# Supplies_ADP2164.net
KiCad netlist of a schematic drawn in Altium Designer
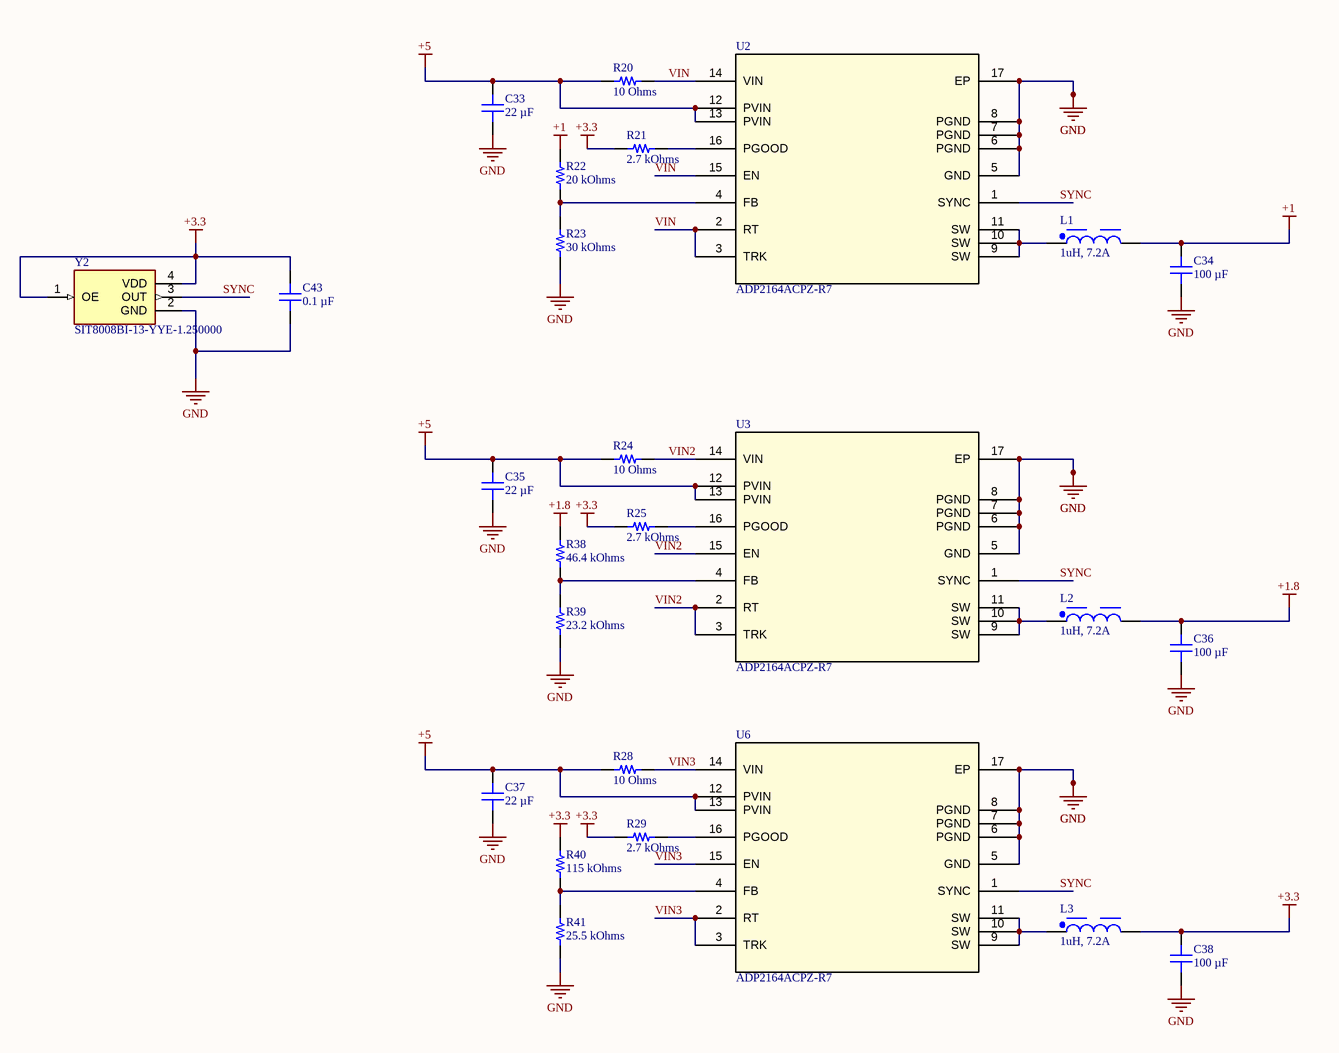
[diagram p0: Supplies_ADP2164.SchDoc]

(export (version "E")
  (design (tool "Eeschema 10.0.6"))
  (components
    (comp (ref "C33")
      (value "22 µF")
      (footprint "CAP 0603_1608")
      (description "CAP CER 22UF 10V X5R 0603")
      (fields
        (field (name "PART NUMBER") "GRM187R61A226ME15D")
        (field (name "MANUFACTURER") "Murata Electronics")
      )
      (libsource (lib "Celestial Altium Library - altium_library") (part "Capacitor"))
    )
    (comp (ref "C34")
      (value "100 µF")
      (footprint "CAP 1210_3225 - 1MM")
      (description "CAP CER 100UF 10V X5R 1210")
      (fields
        (field (name "PART NUMBER") "GRM32ER61A107ME20K")
        (field (name "MANUFACTURER") "Murata Electronics")
      )
      (libsource (lib "Celestial Altium Library - altium_library") (part "Capacitor"))
    )
    (comp (ref "C35")
      (value "22 µF")
      (footprint "CAP 0603_1608")
      (description "CAP CER 22UF 10V X5R 0603")
      (fields
        (field (name "PART NUMBER") "GRM187R61A226ME15D")
        (field (name "MANUFACTURER") "Murata Electronics")
      )
      (libsource (lib "Celestial Altium Library - altium_library") (part "Capacitor"))
    )
    (comp (ref "C36")
      (value "100 µF")
      (footprint "CAP 1210_3225 - 1MM")
      (description "CAP CER 100UF 10V X5R 1210")
      (fields
        (field (name "PART NUMBER") "GRM32ER61A107ME20K")
        (field (name "MANUFACTURER") "Murata Electronics")
      )
      (libsource (lib "Celestial Altium Library - altium_library") (part "Capacitor"))
    )
    (comp (ref "C37")
      (value "22 µF")
      (footprint "CAP 0603_1608")
      (description "CAP CER 22UF 10V X5R 0603")
      (fields
        (field (name "PART NUMBER") "GRM187R61A226ME15D")
        (field (name "MANUFACTURER") "Murata Electronics")
      )
      (libsource (lib "Celestial Altium Library - altium_library") (part "Capacitor"))
    )
    (comp (ref "C38")
      (value "100 µF")
      (footprint "CAP 1210_3225 - 1MM")
      (description "CAP CER 100UF 10V X5R 1210")
      (fields
        (field (name "PART NUMBER") "GRM32ER61A107ME20K")
        (field (name "MANUFACTURER") "Murata Electronics")
      )
      (libsource (lib "Celestial Altium Library - altium_library") (part "Capacitor"))
    )
    (comp (ref "C43")
      (value "0.1 µF")
      (footprint "CAP 0201_0603")
      (description "CAP CER 0.1UF 10V X5R 0201")
      (fields
        (field (name "PART NUMBER") "GRM033R61A104KE15D")
        (field (name "MANUFACTURER") "Murata Electronics")
      )
      (libsource (lib "Celestial Altium Library - altium_library") (part "Capacitor"))
    )
    (comp (ref "L1")
      (value "1uH, 7.2A")
      (footprint "WE-MAPI_4020")
      (description "WE-MAPI SMT Power Inductor, size 4020, 1uH, 7.2A")
      (fields
        (field (name "MANUFACTURER") "Wurth Elektronik")
        (field (name "MANUFACTURER PART NUMBER") "74438356010")
      )
      (libsource (lib "WE-MAPI (rev22a)") (part "74438356010"))
    )
    (comp (ref "L2")
      (value "1uH, 7.2A")
      (footprint "WE-MAPI_4020")
      (description "WE-MAPI SMT Power Inductor, size 4020, 1uH, 7.2A")
      (fields
        (field (name "MANUFACTURER") "Wurth Elektronik")
        (field (name "MANUFACTURER PART NUMBER") "74438356010")
      )
      (libsource (lib "WE-MAPI (rev22a)") (part "74438356010"))
    )
    (comp (ref "L3")
      (value "1uH, 7.2A")
      (footprint "WE-MAPI_4020")
      (description "WE-MAPI SMT Power Inductor, size 4020, 1uH, 7.2A")
      (fields
        (field (name "MANUFACTURER") "Wurth Elektronik")
        (field (name "MANUFACTURER PART NUMBER") "74438356010")
      )
      (libsource (lib "WE-MAPI (rev22a)") (part "74438356010"))
    )
    (comp (ref "R20")
      (value "10 Ohms")
      (footprint "RES 0201_0603")
      (description "RES 10 OHM 5% 1/20W 0201")
      (fields (field (name "PART NUMBER") "RC0201JR-0710RL") (field (name "MANUFACTURER") "Yageo"))
      (libsource (lib "Celestial Altium Library - altium_library") (part "Resistor"))
    )
    (comp (ref "R21")
      (value "2.7 kOhms")
      (footprint "RES 0201_0603")
      (description "RES 2.7K OHM 5% 1/20W 0201 SMD")
      (fields
        (field (name "PART NUMBER") "ERJ-U01J272C")
        (field (name "MANUFACTURER") "Panasonic Electronic Components")
      )
      (libsource (lib "Celestial Altium Library - altium_library") (part "Resistor"))
    )
    (comp (ref "R22")
      (value "20 kOhms")
      (footprint "RES 0201_0603")
      (description "RES SMD 20K OHM 1% 1/20W 0201")
      (fields
        (field (name "PART NUMBER") "ERJ-1GNF2002C")
        (field (name "MANUFACTURER") "Panasonic Electronic Components")
      )
      (libsource (lib "Celestial Altium Library - altium_library") (part "Resistor"))
    )
    (comp (ref "R23")
      (value "30 kOhms")
      (footprint "RES 0201_0603")
      (description "RES SMD 30K OHM 1% 1/20W 0201")
      (fields
        (field (name "PART NUMBER") "ERJ-1GNF3002C")
        (field (name "MANUFACTURER") "Panasonic Electronic Components")
      )
      (libsource (lib "Celestial Altium Library - altium_library") (part "Resistor"))
    )
    (comp (ref "R24")
      (value "10 Ohms")
      (footprint "RES 0201_0603")
      (description "RES 10 OHM 5% 1/20W 0201")
      (fields (field (name "PART NUMBER") "RC0201JR-0710RL") (field (name "MANUFACTURER") "Yageo"))
      (libsource (lib "Celestial Altium Library - altium_library") (part "Resistor"))
    )
    (comp (ref "R25")
      (value "2.7 kOhms")
      (footprint "RES 0201_0603")
      (description "RES 2.7K OHM 5% 1/20W 0201 SMD")
      (fields
        (field (name "PART NUMBER") "ERJ-U01J272C")
        (field (name "MANUFACTURER") "Panasonic Electronic Components")
      )
      (libsource (lib "Celestial Altium Library - altium_library") (part "Resistor"))
    )
    (comp (ref "R28")
      (value "10 Ohms")
      (footprint "RES 0201_0603")
      (description "RES 10 OHM 5% 1/20W 0201")
      (fields (field (name "PART NUMBER") "RC0201JR-0710RL") (field (name "MANUFACTURER") "Yageo"))
      (libsource (lib "Celestial Altium Library - altium_library") (part "Resistor"))
    )
    (comp (ref "R29")
      (value "2.7 kOhms")
      (footprint "RES 0201_0603")
      (description "RES 2.7K OHM 5% 1/20W 0201 SMD")
      (fields
        (field (name "PART NUMBER") "ERJ-U01J272C")
        (field (name "MANUFACTURER") "Panasonic Electronic Components")
      )
      (libsource (lib "Celestial Altium Library - altium_library") (part "Resistor"))
    )
    (comp (ref "R38")
      (value "46.4 kOhms")
      (footprint "RES 0201_0603")
      (description "RES SMD 46.4K OHM 1% 1/20W 0201")
      (fields
        (field (name "PART NUMBER") "ERJ-1GNF4642C")
        (field (name "MANUFACTURER") "Panasonic Electronic Components")
      )
      (libsource (lib "Celestial Altium Library - altium_library") (part "Resistor"))
    )
    (comp (ref "R39")
      (value "23.2 kOhms")
      (footprint "RES 0201_0603")
      (description "RES SMD 23.2K OHM 1% 1/20W 0201")
      (fields
        (field (name "PART NUMBER") "ERJ-1GNF2322C")
        (field (name "MANUFACTURER") "Panasonic Electronic Components")
      )
      (libsource (lib "Celestial Altium Library - altium_library") (part "Resistor"))
    )
    (comp (ref "R40")
      (value "115 kOhms")
      (footprint "RES 0201_0603")
      (description "RES SMD 115K OHM 1% 1/20W 0201")
      (fields
        (field (name "PART NUMBER") "ERJ-1GNF1153C")
        (field (name "MANUFACTURER") "Panasonic Electronic Components")
      )
      (libsource (lib "Celestial Altium Library - altium_library") (part "Resistor"))
    )
    (comp (ref "R41")
      (value "25.5 kOhms")
      (footprint "RES 0201_0603")
      (description "RES SMD 25.5K OHM 1% 1/20W 0201")
      (fields
        (field (name "PART NUMBER") "ERJ-1GNF2552C")
        (field (name "MANUFACTURER") "Panasonic Electronic Components")
      )
      (libsource (lib "Celestial Altium Library - altium_library") (part "Resistor"))
    )
    (comp (ref "U2")
      (value "ADP2164ACPZ-R7")
      (footprint "CP_16_17_ADI")
      (description "No Description Available")
      (fields (field (name "COPYRIGHT") "Copyright (C) 2022 Ultra Librarian. All rights reserved."))
      (libsource (lib "ADP2164ACPZ-R7") (part "ADP2164ACPZ-R7"))
    )
    (comp (ref "U3")
      (value "ADP2164ACPZ-R7")
      (footprint "CP_16_17_ADI")
      (description "No Description Available")
      (fields (field (name "COPYRIGHT") "Copyright (C) 2022 Ultra Librarian. All rights reserved."))
      (libsource (lib "ADP2164ACPZ-R7") (part "ADP2164ACPZ-R7"))
    )
    (comp (ref "U6")
      (value "ADP2164ACPZ-R7")
      (footprint "CP_16_17_ADI")
      (description "No Description Available")
      (fields (field (name "COPYRIGHT") "Copyright (C) 2022 Ultra Librarian. All rights reserved."))
      (libsource (lib "ADP2164ACPZ-R7") (part "ADP2164ACPZ-R7"))
    )
    (comp (ref "Y2")
      (value "SIT8008BI-13-YYE-1.250000")
      (footprint "SIT8008BI-13-33E-33.333330E:OSC_SIT8008BI-13-33E-33.333330E")
      (description "Programmable, Low Power Oscillator, -40 To 85c, 2520, 50ppm, 3.3v, 33.33333mhz, Oe, Smd")
      (fields
        (field (name "MF") "{'manufacturer': u'SiTIME'}")
        (field (name "MP") "SIT8008BI-13-33E-33.333330E")
      )
      (libsource (lib "SIT8008BI-13-33E-33.333330E") (part "SIT8008BI-13-33E-33.333330E"))
    )
  )
  (nets
    (net (code "1") (name "+1") (class "Default")
      (node (ref "C34") (pin "2") (pinfunction "2_2") (pintype "passive"))
      (node (ref "L1") (pin "2") (pinfunction "2_2") (pintype "passive"))
      (node (ref "R22") (pin "2") (pinfunction "2_2") (pintype "passive"))
    )
    (net (code "2") (name "+1.8") (class "Default")
      (node (ref "C36") (pin "2") (pinfunction "2_2") (pintype "passive"))
      (node (ref "L2") (pin "2") (pinfunction "2_2") (pintype "passive"))
      (node (ref "R38") (pin "2") (pinfunction "2_2") (pintype "passive"))
    )
    (net (code "3") (name "+3.3") (class "Default")
      (node (ref "C38") (pin "2") (pinfunction "2_2") (pintype "passive"))
      (node (ref "C43") (pin "2") (pinfunction "2_2") (pintype "passive"))
      (node (ref "L3") (pin "2") (pinfunction "2_2") (pintype "passive"))
      (node (ref "R21") (pin "2") (pinfunction "2_2") (pintype "passive"))
      (node (ref "R25") (pin "2") (pinfunction "2_2") (pintype "passive"))
      (node (ref "R29") (pin "2") (pinfunction "2_2") (pintype "passive"))
      (node (ref "R40") (pin "2") (pinfunction "2_2") (pintype "passive"))
      (node (ref "Y2") (pin "1") (pinfunction "OE_1") (pintype "input"))
      (node (ref "Y2") (pin "4") (pinfunction "VDD_4") (pintype "power_in"))
    )
    (net (code "4") (name "+5") (class "Default")
      (node (ref "C33") (pin "2") (pinfunction "2_2") (pintype "passive"))
      (node (ref "C35") (pin "2") (pinfunction "2_2") (pintype "passive"))
      (node (ref "C37") (pin "2") (pinfunction "2_2") (pintype "passive"))
      (node (ref "R20") (pin "1") (pinfunction "1_1") (pintype "passive"))
      (node (ref "R24") (pin "1") (pinfunction "1_1") (pintype "passive"))
      (node (ref "R28") (pin "1") (pinfunction "1_1") (pintype "passive"))
      (node (ref "U2") (pin "12") (pinfunction "PVIN_12") (pintype "passive"))
      (node (ref "U2") (pin "13") (pinfunction "PVIN_13") (pintype "passive"))
      (node (ref "U3") (pin "12") (pinfunction "PVIN_12") (pintype "passive"))
      (node (ref "U3") (pin "13") (pinfunction "PVIN_13") (pintype "passive"))
      (node (ref "U6") (pin "12") (pinfunction "PVIN_12") (pintype "passive"))
      (node (ref "U6") (pin "13") (pinfunction "PVIN_13") (pintype "passive"))
    )
    (net (code "5") (name "/SYNC") (class "Default")
      (node (ref "U2") (pin "1") (pinfunction "SYNC_1") (pintype "passive"))
      (node (ref "U3") (pin "1") (pinfunction "SYNC_1") (pintype "passive"))
      (node (ref "U6") (pin "1") (pinfunction "SYNC_1") (pintype "passive"))
      (node (ref "Y2") (pin "3") (pinfunction "OUT_3") (pintype "output"))
    )
    (net (code "6") (name "/VIN") (class "Default")
      (node (ref "R20") (pin "2") (pinfunction "2_2") (pintype "passive"))
      (node (ref "U2") (pin "14") (pinfunction "VIN_14") (pintype "passive"))
      (node (ref "U2") (pin "15") (pinfunction "EN_15") (pintype "passive"))
      (node (ref "U2") (pin "2") (pinfunction "RT_2") (pintype "passive"))
      (node (ref "U2") (pin "3") (pinfunction "TRK_3") (pintype "passive"))
    )
    (net (code "7") (name "/VIN2") (class "Default")
      (node (ref "R24") (pin "2") (pinfunction "2_2") (pintype "passive"))
      (node (ref "U3") (pin "14") (pinfunction "VIN_14") (pintype "passive"))
      (node (ref "U3") (pin "15") (pinfunction "EN_15") (pintype "passive"))
      (node (ref "U3") (pin "2") (pinfunction "RT_2") (pintype "passive"))
      (node (ref "U3") (pin "3") (pinfunction "TRK_3") (pintype "passive"))
    )
    (net (code "8") (name "/VIN3") (class "Default")
      (node (ref "R28") (pin "2") (pinfunction "2_2") (pintype "passive"))
      (node (ref "U6") (pin "14") (pinfunction "VIN_14") (pintype "passive"))
      (node (ref "U6") (pin "15") (pinfunction "EN_15") (pintype "passive"))
      (node (ref "U6") (pin "2") (pinfunction "RT_2") (pintype "passive"))
      (node (ref "U6") (pin "3") (pinfunction "TRK_3") (pintype "passive"))
    )
    (net (code "9") (name "GND") (class "Default")
      (node (ref "C33") (pin "1") (pinfunction "1_1") (pintype "passive"))
      (node (ref "C34") (pin "1") (pinfunction "1_1") (pintype "passive"))
      (node (ref "C35") (pin "1") (pinfunction "1_1") (pintype "passive"))
      (node (ref "C36") (pin "1") (pinfunction "1_1") (pintype "passive"))
      (node (ref "C37") (pin "1") (pinfunction "1_1") (pintype "passive"))
      (node (ref "C38") (pin "1") (pinfunction "1_1") (pintype "passive"))
      (node (ref "C43") (pin "1") (pinfunction "1_1") (pintype "passive"))
      (node (ref "R23") (pin "2") (pinfunction "2_2") (pintype "passive"))
      (node (ref "R39") (pin "1") (pinfunction "1_1") (pintype "passive"))
      (node (ref "R41") (pin "1") (pinfunction "1_1") (pintype "passive"))
      (node (ref "U2") (pin "17") (pinfunction "EP_17") (pintype "passive"))
      (node (ref "U2") (pin "5") (pinfunction "GND_5") (pintype "passive"))
      (node (ref "U2") (pin "6") (pinfunction "PGND_6") (pintype "passive"))
      (node (ref "U2") (pin "7") (pinfunction "PGND_7") (pintype "passive"))
      (node (ref "U2") (pin "8") (pinfunction "PGND_8") (pintype "passive"))
      (node (ref "U3") (pin "17") (pinfunction "EP_17") (pintype "passive"))
      (node (ref "U3") (pin "5") (pinfunction "GND_5") (pintype "passive"))
      (node (ref "U3") (pin "6") (pinfunction "PGND_6") (pintype "passive"))
      (node (ref "U3") (pin "7") (pinfunction "PGND_7") (pintype "passive"))
      (node (ref "U3") (pin "8") (pinfunction "PGND_8") (pintype "passive"))
      (node (ref "U6") (pin "17") (pinfunction "EP_17") (pintype "passive"))
      (node (ref "U6") (pin "5") (pinfunction "GND_5") (pintype "passive"))
      (node (ref "U6") (pin "6") (pinfunction "PGND_6") (pintype "passive"))
      (node (ref "U6") (pin "7") (pinfunction "PGND_7") (pintype "passive"))
      (node (ref "U6") (pin "8") (pinfunction "PGND_8") (pintype "passive"))
      (node (ref "Y2") (pin "2") (pinfunction "GND_2") (pintype "power_in"))
    )
    (net (code "10") (name "Net-(L1-Pad1)") (class "Default")
      (node (ref "L1") (pin "1") (pinfunction "1_1") (pintype "passive"))
      (node (ref "U2") (pin "10") (pinfunction "SW_10") (pintype "passive"))
      (node (ref "U2") (pin "11") (pinfunction "SW_11") (pintype "passive"))
      (node (ref "U2") (pin "9") (pinfunction "SW_9") (pintype "passive"))
    )
    (net (code "11") (name "Net-(L2-Pad1)") (class "Default")
      (node (ref "L2") (pin "1") (pinfunction "1_1") (pintype "passive"))
      (node (ref "U3") (pin "10") (pinfunction "SW_10") (pintype "passive"))
      (node (ref "U3") (pin "11") (pinfunction "SW_11") (pintype "passive"))
      (node (ref "U3") (pin "9") (pinfunction "SW_9") (pintype "passive"))
    )
    (net (code "12") (name "Net-(L3-Pad1)") (class "Default")
      (node (ref "L3") (pin "1") (pinfunction "1_1") (pintype "passive"))
      (node (ref "U6") (pin "10") (pinfunction "SW_10") (pintype "passive"))
      (node (ref "U6") (pin "11") (pinfunction "SW_11") (pintype "passive"))
      (node (ref "U6") (pin "9") (pinfunction "SW_9") (pintype "passive"))
    )
    (net (code "13") (name "Net-(U2-FB)") (class "Default")
      (node (ref "R22") (pin "1") (pinfunction "1_1") (pintype "passive"))
      (node (ref "R23") (pin "1") (pinfunction "1_1") (pintype "passive"))
      (node (ref "U2") (pin "4") (pinfunction "FB_4") (pintype "passive"))
    )
    (net (code "14") (name "Net-(U2-PGOOD)") (class "Default")
      (node (ref "R21") (pin "1") (pinfunction "1_1") (pintype "passive"))
      (node (ref "U2") (pin "16") (pinfunction "PGOOD_16") (pintype "passive"))
    )
    (net (code "15") (name "Net-(U3-FB)") (class "Default")
      (node (ref "R38") (pin "1") (pinfunction "1_1") (pintype "passive"))
      (node (ref "R39") (pin "2") (pinfunction "2_2") (pintype "passive"))
      (node (ref "U3") (pin "4") (pinfunction "FB_4") (pintype "passive"))
    )
    (net (code "16") (name "Net-(U3-PGOOD)") (class "Default")
      (node (ref "R25") (pin "1") (pinfunction "1_1") (pintype "passive"))
      (node (ref "U3") (pin "16") (pinfunction "PGOOD_16") (pintype "passive"))
    )
    (net (code "17") (name "Net-(U6-FB)") (class "Default")
      (node (ref "R40") (pin "1") (pinfunction "1_1") (pintype "passive"))
      (node (ref "R41") (pin "2") (pinfunction "2_2") (pintype "passive"))
      (node (ref "U6") (pin "4") (pinfunction "FB_4") (pintype "passive"))
    )
    (net (code "18") (name "Net-(U6-PGOOD)") (class "Default")
      (node (ref "R29") (pin "1") (pinfunction "1_1") (pintype "passive"))
      (node (ref "U6") (pin "16") (pinfunction "PGOOD_16") (pintype "passive"))
    )
  )
)
